# 04_-_PWR_2V5_1V8_1V35.net
KiCad netlist of a schematic drawn in Altium Designer
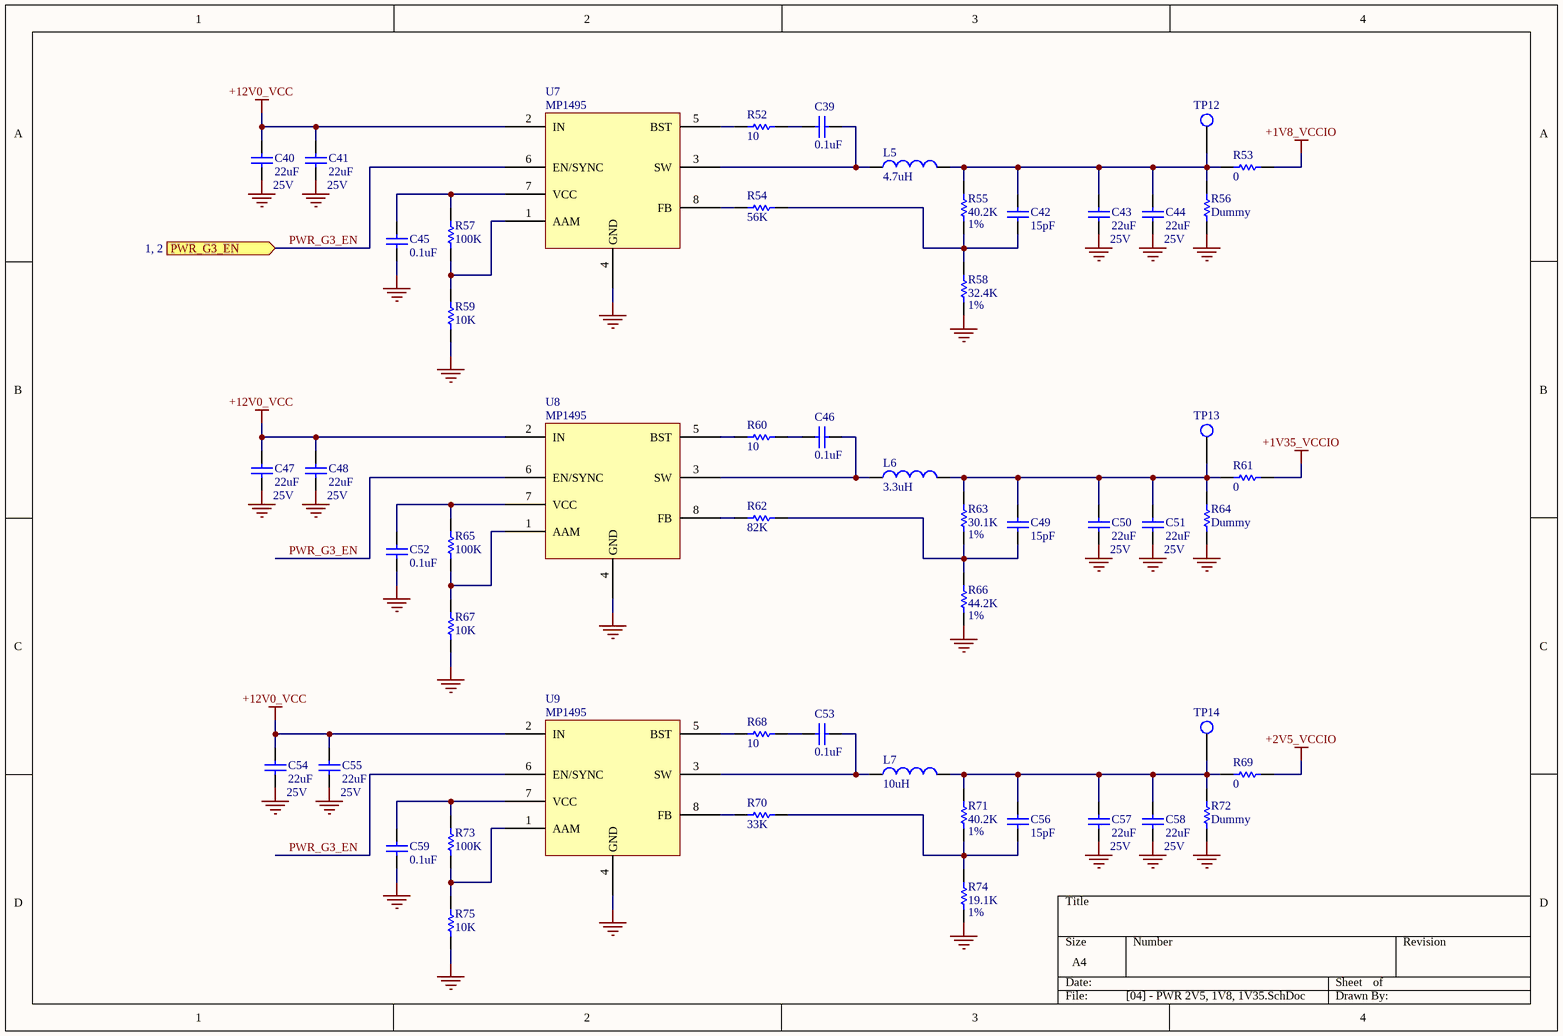
[diagram p0: [04] - PWR 2V5, 1V8, 1V35.SchDoc]

(export (version "E")
  (design (tool "Eeschema 10.0.6"))
  (components
    (comp (ref "C39")
      (value "0.1uF")
      (footprint "0402_C")
      (description "Non-Pol SMD Capacitor")
      (libsource (lib "Passive Components") (part "Cap SMD"))
    )
    (comp (ref "C40")
      (value "22uF")
      (footprint "1210_C")
      (description "Non-Pol SMD Capacitor")
      (fields (field (name "RATED_VOLTAGE") "25V") (field (name "MANUFACTURER PART NUM") "GRM32ER71E226KE15"))
      (libsource (lib "Passive Components") (part "Cap SMD"))
    )
    (comp (ref "C41")
      (value "22uF")
      (footprint "1210_C")
      (description "Non-Pol SMD Capacitor")
      (fields (field (name "RATED_VOLTAGE") "25V") (field (name "MANUFACTURER PART NUM") "GRM32ER71E226KE15"))
      (libsource (lib "Passive Components") (part "Cap SMD"))
    )
    (comp (ref "C42")
      (value "15pF")
      (footprint "0402_C")
      (description "Non-Pol SMD Capacitor")
      (libsource (lib "Passive Components") (part "Cap SMD"))
    )
    (comp (ref "C43")
      (value "22uF")
      (footprint "1210_C")
      (description "Non-Pol SMD Capacitor")
      (fields (field (name "RATED_VOLTAGE") "25V") (field (name "MANUFACTURER PART NUM") "GRM32ER71E226KE15"))
      (libsource (lib "Passive Components") (part "Cap SMD"))
    )
    (comp (ref "C44")
      (value "22uF")
      (footprint "1210_C")
      (description "Non-Pol SMD Capacitor")
      (fields (field (name "RATED_VOLTAGE") "25V") (field (name "MANUFACTURER PART NUM") "GRM32ER71E226KE15"))
      (libsource (lib "Passive Components") (part "Cap SMD"))
    )
    (comp (ref "C45")
      (value "0.1uF")
      (footprint "0402_C")
      (description "Non-Pol SMD Capacitor")
      (libsource (lib "Passive Components") (part "Cap SMD"))
    )
    (comp (ref "C46")
      (value "0.1uF")
      (footprint "0402_C")
      (description "Non-Pol SMD Capacitor")
      (libsource (lib "Passive Components") (part "Cap SMD"))
    )
    (comp (ref "C47")
      (value "22uF")
      (footprint "1210_C")
      (description "Non-Pol SMD Capacitor")
      (fields (field (name "RATED_VOLTAGE") "25V") (field (name "MANUFACTURER PART NUM") "GRM32ER71E226KE15"))
      (libsource (lib "Passive Components") (part "Cap SMD"))
    )
    (comp (ref "C48")
      (value "22uF")
      (footprint "1210_C")
      (description "Non-Pol SMD Capacitor")
      (fields (field (name "RATED_VOLTAGE") "25V") (field (name "MANUFACTURER PART NUM") "GRM32ER71E226KE15"))
      (libsource (lib "Passive Components") (part "Cap SMD"))
    )
    (comp (ref "C49")
      (value "15pF")
      (footprint "0402_C")
      (description "Non-Pol SMD Capacitor")
      (libsource (lib "Passive Components") (part "Cap SMD"))
    )
    (comp (ref "C50")
      (value "22uF")
      (footprint "1210_C")
      (description "Non-Pol SMD Capacitor")
      (fields (field (name "RATED_VOLTAGE") "25V") (field (name "MANUFACTURER PART NUM") "GRM32ER71E226KE15"))
      (libsource (lib "Passive Components") (part "Cap SMD"))
    )
    (comp (ref "C51")
      (value "22uF")
      (footprint "1210_C")
      (description "Non-Pol SMD Capacitor")
      (fields (field (name "RATED_VOLTAGE") "25V") (field (name "MANUFACTURER PART NUM") "GRM32ER71E226KE15"))
      (libsource (lib "Passive Components") (part "Cap SMD"))
    )
    (comp (ref "C52")
      (value "0.1uF")
      (footprint "0402_C")
      (description "Non-Pol SMD Capacitor")
      (libsource (lib "Passive Components") (part "Cap SMD"))
    )
    (comp (ref "C53")
      (value "0.1uF")
      (footprint "0402_C")
      (description "Non-Pol SMD Capacitor")
      (libsource (lib "Passive Components") (part "Cap SMD"))
    )
    (comp (ref "C54")
      (value "22uF")
      (footprint "1210_C")
      (description "Non-Pol SMD Capacitor")
      (fields (field (name "RATED_VOLTAGE") "25V") (field (name "MANUFACTURER PART NUM") "GRM32ER71E226KE15"))
      (libsource (lib "Passive Components") (part "Cap SMD"))
    )
    (comp (ref "C55")
      (value "22uF")
      (footprint "1210_C")
      (description "Non-Pol SMD Capacitor")
      (fields (field (name "RATED_VOLTAGE") "25V") (field (name "MANUFACTURER PART NUM") "GRM32ER71E226KE15"))
      (libsource (lib "Passive Components") (part "Cap SMD"))
    )
    (comp (ref "C56")
      (value "15pF")
      (footprint "0402_C")
      (description "Non-Pol SMD Capacitor")
      (libsource (lib "Passive Components") (part "Cap SMD"))
    )
    (comp (ref "C57")
      (value "22uF")
      (footprint "1210_C")
      (description "Non-Pol SMD Capacitor")
      (fields (field (name "RATED_VOLTAGE") "25V") (field (name "MANUFACTURER PART NUM") "GRM32ER71E226KE15"))
      (libsource (lib "Passive Components") (part "Cap SMD"))
    )
    (comp (ref "C58")
      (value "22uF")
      (footprint "1210_C")
      (description "Non-Pol SMD Capacitor")
      (fields (field (name "RATED_VOLTAGE") "25V") (field (name "MANUFACTURER PART NUM") "GRM32ER71E226KE15"))
      (libsource (lib "Passive Components") (part "Cap SMD"))
    )
    (comp (ref "C59")
      (value "0.1uF")
      (footprint "0402_C")
      (description "Non-Pol SMD Capacitor")
      (libsource (lib "Passive Components") (part "Cap SMD"))
    )
    (comp (ref "L5")
      (value "4.7uH")
      (footprint "IHLP-2525")
      (description "Inductor SMD")
      (fields (field (name "MANUFACTURER PART NUM") "IHLP2525CZER4R7M01"))
      (libsource (lib "Passive Components") (part "Inductor"))
    )
    (comp (ref "L6")
      (value "3.3uH")
      (footprint "IHLP-2020")
      (description "Inductor SMD")
      (fields (field (name "MANUFACTURER PART NUM") "IHLP2020BZER3R3M5A"))
      (libsource (lib "Passive Components") (part "Inductor"))
    )
    (comp (ref "L7")
      (value "10uH")
      (footprint "IHLP-2525")
      (description "Inductor SMD")
      (fields (field (name "MANUFACTURER PART NUM") "IHLP2525CZER100M01"))
      (libsource (lib "Passive Components") (part "Inductor"))
    )
    (comp (ref "R52")
      (value "10")
      (footprint "0402_R")
      (description "SMD Resistor")
      (fields (field (name "TOLERANCE") "5%"))
      (libsource (lib "Passive Components") (part "Res SMD"))
    )
    (comp (ref "R53")
      (value "0")
      (footprint "1210_R")
      (description "SMD Resistor")
      (fields (field (name "TOLERANCE") "5%"))
      (libsource (lib "Passive Components") (part "Res SMD"))
    )
    (comp (ref "R54")
      (value "56K")
      (footprint "0402_R")
      (description "SMD Resistor")
      (fields (field (name "TOLERANCE") "5%"))
      (libsource (lib "Passive Components") (part "Res SMD"))
    )
    (comp (ref "R55")
      (value "40.2K")
      (footprint "0402_R")
      (description "SMD Resistor")
      (fields (field (name "TOLERANCE") "1%"))
      (libsource (lib "Passive Components") (part "Res SMD"))
    )
    (comp (ref "R56")
      (value "Dummy")
      (footprint "1210_R")
      (description "SMD Resistor")
      (fields (field (name "TOLERANCE") "5%"))
      (libsource (lib "Passive Components") (part "Res SMD"))
    )
    (comp (ref "R57")
      (value "100K")
      (footprint "0402_R")
      (description "SMD Resistor")
      (fields (field (name "TOLERANCE") "5%"))
      (libsource (lib "Passive Components") (part "Res SMD"))
    )
    (comp (ref "R58")
      (value "32.4K")
      (footprint "0402_R")
      (description "SMD Resistor")
      (fields (field (name "TOLERANCE") "1%"))
      (libsource (lib "Passive Components") (part "Res SMD"))
    )
    (comp (ref "R59")
      (value "10K")
      (footprint "0402_R")
      (description "SMD Resistor")
      (fields (field (name "TOLERANCE") "5%"))
      (libsource (lib "Passive Components") (part "Res SMD"))
    )
    (comp (ref "R60")
      (value "10")
      (footprint "0402_R")
      (description "SMD Resistor")
      (fields (field (name "TOLERANCE") "5%"))
      (libsource (lib "Passive Components") (part "Res SMD"))
    )
    (comp (ref "R61")
      (value "0")
      (footprint "1210_R")
      (description "SMD Resistor")
      (fields (field (name "TOLERANCE") "5%"))
      (libsource (lib "Passive Components") (part "Res SMD"))
    )
    (comp (ref "R62")
      (value "82K")
      (footprint "0402_R")
      (description "SMD Resistor")
      (fields (field (name "TOLERANCE") "5%"))
      (libsource (lib "Passive Components") (part "Res SMD"))
    )
    (comp (ref "R63")
      (value "30.1K")
      (footprint "0402_R")
      (description "SMD Resistor")
      (fields (field (name "TOLERANCE") "1%"))
      (libsource (lib "Passive Components") (part "Res SMD"))
    )
    (comp (ref "R64")
      (value "Dummy")
      (footprint "1210_R")
      (description "SMD Resistor")
      (fields (field (name "TOLERANCE") "5%"))
      (libsource (lib "Passive Components") (part "Res SMD"))
    )
    (comp (ref "R65")
      (value "100K")
      (footprint "0402_R")
      (description "SMD Resistor")
      (fields (field (name "TOLERANCE") "5%"))
      (libsource (lib "Passive Components") (part "Res SMD"))
    )
    (comp (ref "R66")
      (value "44.2K")
      (footprint "0402_R")
      (description "SMD Resistor")
      (fields (field (name "TOLERANCE") "1%"))
      (libsource (lib "Passive Components") (part "Res SMD"))
    )
    (comp (ref "R67")
      (value "10K")
      (footprint "0402_R")
      (description "SMD Resistor")
      (fields (field (name "TOLERANCE") "5%"))
      (libsource (lib "Passive Components") (part "Res SMD"))
    )
    (comp (ref "R68")
      (value "10")
      (footprint "0402_R")
      (description "SMD Resistor")
      (fields (field (name "TOLERANCE") "5%"))
      (libsource (lib "Passive Components") (part "Res SMD"))
    )
    (comp (ref "R69")
      (value "0")
      (footprint "1210_R")
      (description "SMD Resistor")
      (fields (field (name "TOLERANCE") "5%"))
      (libsource (lib "Passive Components") (part "Res SMD"))
    )
    (comp (ref "R70")
      (value "33K")
      (footprint "0402_R")
      (description "SMD Resistor")
      (fields (field (name "TOLERANCE") "5%"))
      (libsource (lib "Passive Components") (part "Res SMD"))
    )
    (comp (ref "R71")
      (value "40.2K")
      (footprint "0402_R")
      (description "SMD Resistor")
      (fields (field (name "TOLERANCE") "1%"))
      (libsource (lib "Passive Components") (part "Res SMD"))
    )
    (comp (ref "R72")
      (value "Dummy")
      (footprint "1210_R")
      (description "SMD Resistor")
      (fields (field (name "TOLERANCE") "5%"))
      (libsource (lib "Passive Components") (part "Res SMD"))
    )
    (comp (ref "R73")
      (value "100K")
      (footprint "0402_R")
      (description "SMD Resistor")
      (fields (field (name "TOLERANCE") "5%"))
      (libsource (lib "Passive Components") (part "Res SMD"))
    )
    (comp (ref "R74")
      (value "19.1K")
      (footprint "0402_R")
      (description "SMD Resistor")
      (fields (field (name "TOLERANCE") "1%"))
      (libsource (lib "Passive Components") (part "Res SMD"))
    )
    (comp (ref "R75")
      (value "10K")
      (footprint "0402_R")
      (description "SMD Resistor")
      (fields (field (name "TOLERANCE") "5%"))
      (libsource (lib "Passive Components") (part "Res SMD"))
    )
    (comp (ref "TP12")
      (value "Test Point")
      (footprint "PIN_1.5mm")
      (description "Test Point Footprint")
      (libsource (lib "Passive Components") (part "Test Point"))
    )
    (comp (ref "TP13")
      (value "Test Point")
      (footprint "PIN_1.5mm")
      (description "Test Point Footprint")
      (libsource (lib "Passive Components") (part "Test Point"))
    )
    (comp (ref "TP14")
      (value "Test Point")
      (footprint "PIN_1.5mm")
      (description "Test Point Footprint")
      (libsource (lib "Passive Components") (part "Test Point"))
    )
    (comp (ref "U7")
      (value "MP1495")
      (footprint "TSOT23-8")
      (description "High Efficiency 3A, 16V, 500kHz Synchronous Step Down Converter")
      (fields (field (name "MANUFACTURER PART NUM") "MP1495SGJ-Z"))
      (libsource (lib "Project_schlib") (part "MP1495"))
    )
    (comp (ref "U8")
      (value "MP1495")
      (footprint "TSOT23-8")
      (description "High Efficiency 3A, 16V, 500kHz Synchronous Step Down Converter")
      (fields (field (name "MANUFACTURER PART NUM") "MP1495SGJ-Z"))
      (libsource (lib "Project_schlib") (part "MP1495"))
    )
    (comp (ref "U9")
      (value "MP1495")
      (footprint "TSOT23-8")
      (description "High Efficiency 3A, 16V, 500kHz Synchronous Step Down Converter")
      (fields (field (name "MANUFACTURER PART NUM") "MP1495SGJ-Z"))
      (libsource (lib "Project_schlib") (part "MP1495"))
    )
  )
  (nets
    (net (code "1") (name "+1V8_VCCIO") (class "Default")
      (node (ref "R53") (pin "2") (pinfunction "2_2") (pintype "passive"))
    )
    (net (code "2") (name "+1V35_VCCIO") (class "Default")
      (node (ref "R61") (pin "2") (pinfunction "2_2") (pintype "passive"))
    )
    (net (code "3") (name "+2V5_VCCIO") (class "Default")
      (node (ref "R69") (pin "2") (pinfunction "2_2") (pintype "passive"))
    )
    (net (code "4") (name "+12V0_VCC") (class "Default")
      (node (ref "C40") (pin "2") (pinfunction "2_2") (pintype "passive"))
      (node (ref "C41") (pin "2") (pinfunction "2_2") (pintype "passive"))
      (node (ref "C47") (pin "2") (pinfunction "2_2") (pintype "passive"))
      (node (ref "C48") (pin "2") (pinfunction "2_2") (pintype "passive"))
      (node (ref "C54") (pin "2") (pinfunction "2_2") (pintype "passive"))
      (node (ref "C55") (pin "2") (pinfunction "2_2") (pintype "passive"))
      (node (ref "U7") (pin "2") (pinfunction "IN_2") (pintype "passive"))
      (node (ref "U8") (pin "2") (pinfunction "IN_2") (pintype "passive"))
      (node (ref "U9") (pin "2") (pinfunction "IN_2") (pintype "passive"))
    )
    (net (code "5") (name "/PWR_G3_EN") (class "Default")
      (node (ref "U7") (pin "6") (pinfunction "EN/SYNC_6") (pintype "passive"))
      (node (ref "U8") (pin "6") (pinfunction "EN/SYNC_6") (pintype "passive"))
      (node (ref "U9") (pin "6") (pinfunction "EN/SYNC_6") (pintype "passive"))
    )
    (net (code "6") (name "GND") (class "Default")
      (node (ref "C40") (pin "1") (pinfunction "1_1") (pintype "passive"))
      (node (ref "C41") (pin "1") (pinfunction "1_1") (pintype "passive"))
      (node (ref "C43") (pin "1") (pinfunction "1_1") (pintype "passive"))
      (node (ref "C44") (pin "1") (pinfunction "1_1") (pintype "passive"))
      (node (ref "C45") (pin "1") (pinfunction "1_1") (pintype "passive"))
      (node (ref "C47") (pin "1") (pinfunction "1_1") (pintype "passive"))
      (node (ref "C48") (pin "1") (pinfunction "1_1") (pintype "passive"))
      (node (ref "C50") (pin "1") (pinfunction "1_1") (pintype "passive"))
      (node (ref "C51") (pin "1") (pinfunction "1_1") (pintype "passive"))
      (node (ref "C52") (pin "1") (pinfunction "1_1") (pintype "passive"))
      (node (ref "C54") (pin "1") (pinfunction "1_1") (pintype "passive"))
      (node (ref "C55") (pin "1") (pinfunction "1_1") (pintype "passive"))
      (node (ref "C57") (pin "1") (pinfunction "1_1") (pintype "passive"))
      (node (ref "C58") (pin "1") (pinfunction "1_1") (pintype "passive"))
      (node (ref "C59") (pin "1") (pinfunction "1_1") (pintype "passive"))
      (node (ref "R56") (pin "1") (pinfunction "1_1") (pintype "passive"))
      (node (ref "R58") (pin "1") (pinfunction "1_1") (pintype "passive"))
      (node (ref "R59") (pin "1") (pinfunction "1_1") (pintype "passive"))
      (node (ref "R64") (pin "1") (pinfunction "1_1") (pintype "passive"))
      (node (ref "R66") (pin "1") (pinfunction "1_1") (pintype "passive"))
      (node (ref "R67") (pin "1") (pinfunction "1_1") (pintype "passive"))
      (node (ref "R72") (pin "1") (pinfunction "1_1") (pintype "passive"))
      (node (ref "R74") (pin "1") (pinfunction "1_1") (pintype "passive"))
      (node (ref "R75") (pin "1") (pinfunction "1_1") (pintype "passive"))
      (node (ref "U7") (pin "4") (pinfunction "GND_4") (pintype "passive"))
      (node (ref "U8") (pin "4") (pinfunction "GND_4") (pintype "passive"))
      (node (ref "U9") (pin "4") (pinfunction "GND_4") (pintype "passive"))
    )
    (net (code "7") (name "Net-(C39-Pad1)") (class "Default")
      (node (ref "C39") (pin "1") (pinfunction "1_1") (pintype "passive"))
      (node (ref "R52") (pin "2") (pinfunction "2_2") (pintype "passive"))
    )
    (net (code "8") (name "Net-(C42-Pad1)") (class "Default")
      (node (ref "C42") (pin "1") (pinfunction "1_1") (pintype "passive"))
      (node (ref "R54") (pin "2") (pinfunction "2_2") (pintype "passive"))
      (node (ref "R55") (pin "1") (pinfunction "1_1") (pintype "passive"))
      (node (ref "R58") (pin "2") (pinfunction "2_2") (pintype "passive"))
    )
    (net (code "9") (name "Net-(C42-Pad2)") (class "Default")
      (node (ref "C42") (pin "2") (pinfunction "2_2") (pintype "passive"))
      (node (ref "C43") (pin "2") (pinfunction "2_2") (pintype "passive"))
      (node (ref "C44") (pin "2") (pinfunction "2_2") (pintype "passive"))
      (node (ref "L5") (pin "2") (pinfunction "2_2") (pintype "passive"))
      (node (ref "R53") (pin "1") (pinfunction "1_1") (pintype "passive"))
      (node (ref "R55") (pin "2") (pinfunction "2_2") (pintype "passive"))
      (node (ref "R56") (pin "2") (pinfunction "2_2") (pintype "passive"))
      (node (ref "TP12") (pin "1") (pinfunction "1_1") (pintype "passive"))
    )
    (net (code "10") (name "Net-(C46-Pad1)") (class "Default")
      (node (ref "C46") (pin "1") (pinfunction "1_1") (pintype "passive"))
      (node (ref "R60") (pin "2") (pinfunction "2_2") (pintype "passive"))
    )
    (net (code "11") (name "Net-(C49-Pad1)") (class "Default")
      (node (ref "C49") (pin "1") (pinfunction "1_1") (pintype "passive"))
      (node (ref "R62") (pin "2") (pinfunction "2_2") (pintype "passive"))
      (node (ref "R63") (pin "1") (pinfunction "1_1") (pintype "passive"))
      (node (ref "R66") (pin "2") (pinfunction "2_2") (pintype "passive"))
    )
    (net (code "12") (name "Net-(C49-Pad2)") (class "Default")
      (node (ref "C49") (pin "2") (pinfunction "2_2") (pintype "passive"))
      (node (ref "C50") (pin "2") (pinfunction "2_2") (pintype "passive"))
      (node (ref "C51") (pin "2") (pinfunction "2_2") (pintype "passive"))
      (node (ref "L6") (pin "2") (pinfunction "2_2") (pintype "passive"))
      (node (ref "R61") (pin "1") (pinfunction "1_1") (pintype "passive"))
      (node (ref "R63") (pin "2") (pinfunction "2_2") (pintype "passive"))
      (node (ref "R64") (pin "2") (pinfunction "2_2") (pintype "passive"))
      (node (ref "TP13") (pin "1") (pinfunction "1_1") (pintype "passive"))
    )
    (net (code "13") (name "Net-(C53-Pad1)") (class "Default")
      (node (ref "C53") (pin "1") (pinfunction "1_1") (pintype "passive"))
      (node (ref "R68") (pin "2") (pinfunction "2_2") (pintype "passive"))
    )
    (net (code "14") (name "Net-(C56-Pad1)") (class "Default")
      (node (ref "C56") (pin "1") (pinfunction "1_1") (pintype "passive"))
      (node (ref "R70") (pin "2") (pinfunction "2_2") (pintype "passive"))
      (node (ref "R71") (pin "1") (pinfunction "1_1") (pintype "passive"))
      (node (ref "R74") (pin "2") (pinfunction "2_2") (pintype "passive"))
    )
    (net (code "15") (name "Net-(C56-Pad2)") (class "Default")
      (node (ref "C56") (pin "2") (pinfunction "2_2") (pintype "passive"))
      (node (ref "C57") (pin "2") (pinfunction "2_2") (pintype "passive"))
      (node (ref "C58") (pin "2") (pinfunction "2_2") (pintype "passive"))
      (node (ref "L7") (pin "2") (pinfunction "2_2") (pintype "passive"))
      (node (ref "R69") (pin "1") (pinfunction "1_1") (pintype "passive"))
      (node (ref "R71") (pin "2") (pinfunction "2_2") (pintype "passive"))
      (node (ref "R72") (pin "2") (pinfunction "2_2") (pintype "passive"))
      (node (ref "TP14") (pin "1") (pinfunction "1_1") (pintype "passive"))
    )
    (net (code "16") (name "Net-(U7-AAM)") (class "Default")
      (node (ref "R57") (pin "1") (pinfunction "1_1") (pintype "passive"))
      (node (ref "R59") (pin "2") (pinfunction "2_2") (pintype "passive"))
      (node (ref "U7") (pin "1") (pinfunction "AAM_1") (pintype "passive"))
    )
    (net (code "17") (name "Net-(U7-BST)") (class "Default")
      (node (ref "R52") (pin "1") (pinfunction "1_1") (pintype "passive"))
      (node (ref "U7") (pin "5") (pinfunction "BST_5") (pintype "passive"))
    )
    (net (code "18") (name "Net-(U7-FB)") (class "Default")
      (node (ref "R54") (pin "1") (pinfunction "1_1") (pintype "passive"))
      (node (ref "U7") (pin "8") (pinfunction "FB_8") (pintype "passive"))
    )
    (net (code "19") (name "Net-(U7-SW)") (class "Default")
      (node (ref "C39") (pin "2") (pinfunction "2_2") (pintype "passive"))
      (node (ref "L5") (pin "1") (pinfunction "1_1") (pintype "passive"))
      (node (ref "U7") (pin "3") (pinfunction "SW_3") (pintype "passive"))
    )
    (net (code "20") (name "Net-(U7-VCC)") (class "Default")
      (node (ref "C45") (pin "2") (pinfunction "2_2") (pintype "passive"))
      (node (ref "R57") (pin "2") (pinfunction "2_2") (pintype "passive"))
      (node (ref "U7") (pin "7") (pinfunction "VCC_7") (pintype "passive"))
    )
    (net (code "21") (name "Net-(U8-AAM)") (class "Default")
      (node (ref "R65") (pin "1") (pinfunction "1_1") (pintype "passive"))
      (node (ref "R67") (pin "2") (pinfunction "2_2") (pintype "passive"))
      (node (ref "U8") (pin "1") (pinfunction "AAM_1") (pintype "passive"))
    )
    (net (code "22") (name "Net-(U8-BST)") (class "Default")
      (node (ref "R60") (pin "1") (pinfunction "1_1") (pintype "passive"))
      (node (ref "U8") (pin "5") (pinfunction "BST_5") (pintype "passive"))
    )
    (net (code "23") (name "Net-(U8-FB)") (class "Default")
      (node (ref "R62") (pin "1") (pinfunction "1_1") (pintype "passive"))
      (node (ref "U8") (pin "8") (pinfunction "FB_8") (pintype "passive"))
    )
    (net (code "24") (name "Net-(U8-SW)") (class "Default")
      (node (ref "C46") (pin "2") (pinfunction "2_2") (pintype "passive"))
      (node (ref "L6") (pin "1") (pinfunction "1_1") (pintype "passive"))
      (node (ref "U8") (pin "3") (pinfunction "SW_3") (pintype "passive"))
    )
    (net (code "25") (name "Net-(U8-VCC)") (class "Default")
      (node (ref "C52") (pin "2") (pinfunction "2_2") (pintype "passive"))
      (node (ref "R65") (pin "2") (pinfunction "2_2") (pintype "passive"))
      (node (ref "U8") (pin "7") (pinfunction "VCC_7") (pintype "passive"))
    )
    (net (code "26") (name "Net-(U9-AAM)") (class "Default")
      (node (ref "R73") (pin "1") (pinfunction "1_1") (pintype "passive"))
      (node (ref "R75") (pin "2") (pinfunction "2_2") (pintype "passive"))
      (node (ref "U9") (pin "1") (pinfunction "AAM_1") (pintype "passive"))
    )
    (net (code "27") (name "Net-(U9-BST)") (class "Default")
      (node (ref "R68") (pin "1") (pinfunction "1_1") (pintype "passive"))
      (node (ref "U9") (pin "5") (pinfunction "BST_5") (pintype "passive"))
    )
    (net (code "28") (name "Net-(U9-FB)") (class "Default")
      (node (ref "R70") (pin "1") (pinfunction "1_1") (pintype "passive"))
      (node (ref "U9") (pin "8") (pinfunction "FB_8") (pintype "passive"))
    )
    (net (code "29") (name "Net-(U9-SW)") (class "Default")
      (node (ref "C53") (pin "2") (pinfunction "2_2") (pintype "passive"))
      (node (ref "L7") (pin "1") (pinfunction "1_1") (pintype "passive"))
      (node (ref "U9") (pin "3") (pinfunction "SW_3") (pintype "passive"))
    )
    (net (code "30") (name "Net-(U9-VCC)") (class "Default")
      (node (ref "C59") (pin "2") (pinfunction "2_2") (pintype "passive"))
      (node (ref "R73") (pin "2") (pinfunction "2_2") (pintype "passive"))
      (node (ref "U9") (pin "7") (pinfunction "VCC_7") (pintype "passive"))
    )
  )
)
